# AND_operations.net
KiCad netlist of a schematic drawn in Altium Designer
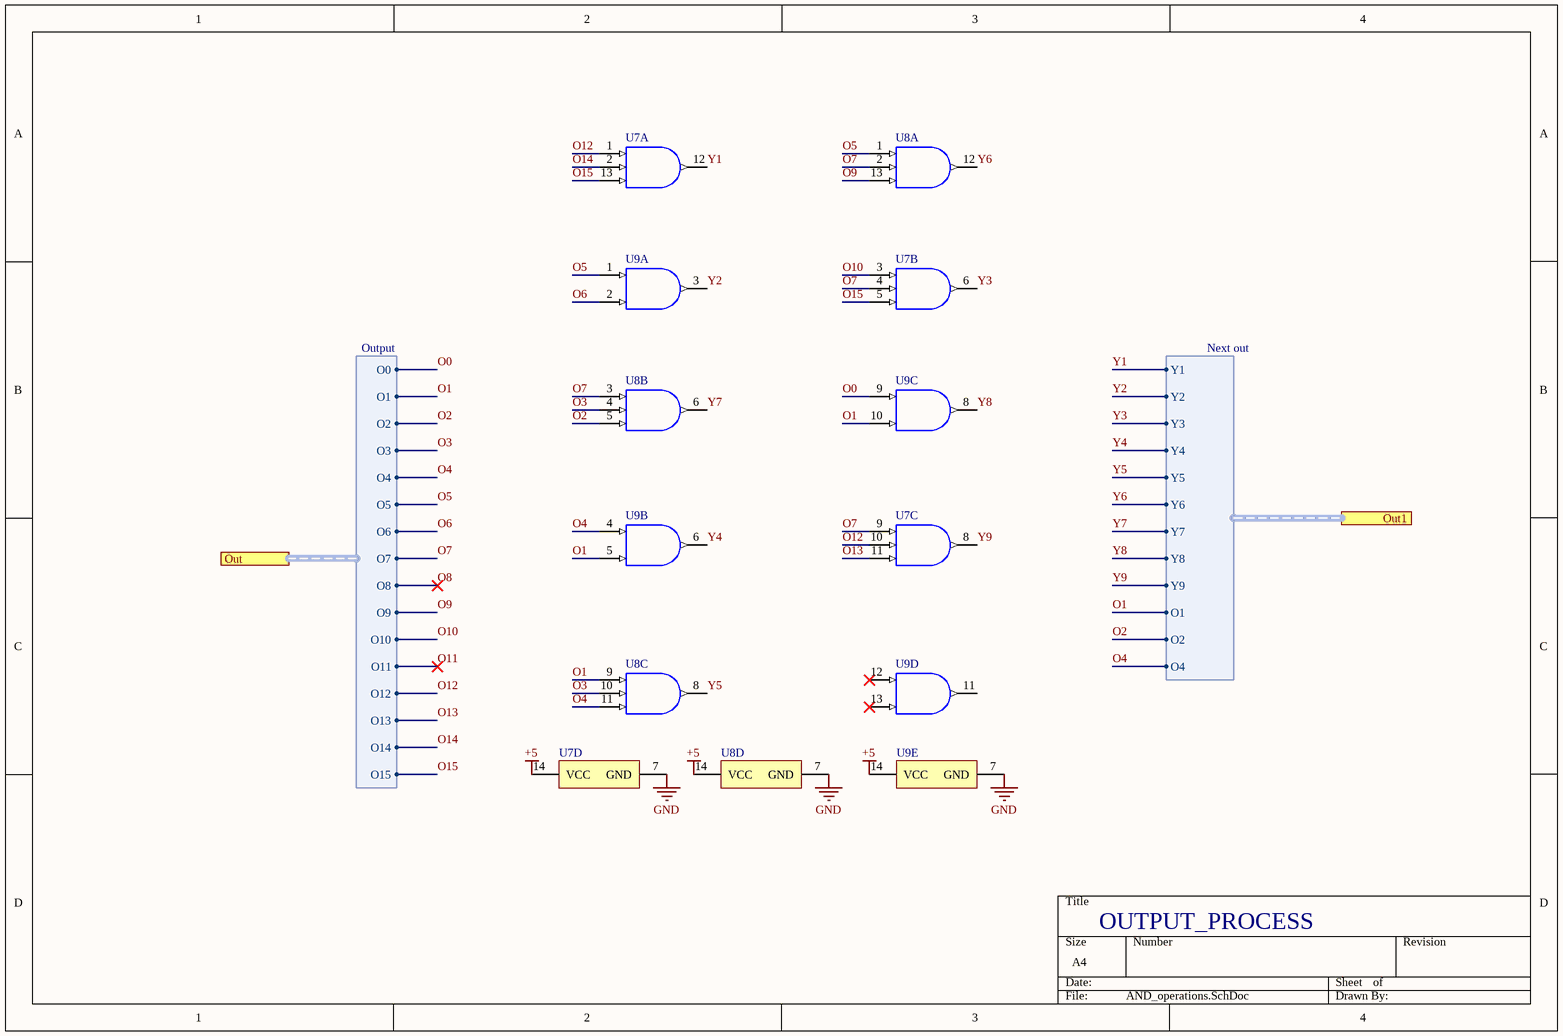
[diagram p0: AND_operations.SchDoc]

(export (version "E")
  (design (tool "Eeschema 10.0.6"))
  (components
    (comp (ref "U7")
      (value "SN74LS11N")
      (footprint "N0014A")
      (description "Triple 3-input positive-AND gates, N0014A, TUBE")
      (fields
        (field (name "MANUFACTURER") "Texas Instruments")
        (field (name "GENERIC PART NUMBER") "SN74LS11")
      )
      (libsource (lib "Altium Content Vault") (part "TI-AND-3-3IN-14"))
    )
    (comp (ref "U8")
      (value "SN74LS11N")
      (footprint "N0014A")
      (description "Triple 3-input positive-AND gates, N0014A, TUBE")
      (fields
        (field (name "MANUFACTURER") "Texas Instruments")
        (field (name "GENERIC PART NUMBER") "SN74LS11")
      )
      (libsource (lib "Altium Content Vault") (part "TI-AND-3-3IN-14"))
    )
    (comp (ref "U9")
      (value "SN74S08N")
      (footprint "N0014A")
      (description "Quad 2-input positive-AND gates, N0014A, TUBE")
      (fields
        (field (name "MANUFACTURER") "Texas Instruments")
        (field (name "GENERIC PART NUMBER") "SN74S08")
      )
      (libsource (lib "Altium Content Vault") (part "TI-AND-4-2IN-14"))
    )
  )
  (nets
    (net (code "4") (name "+5") (class "Default")
      (node (ref "U7") (pin "14") (pinfunction "VCC_14") (pintype "power_in"))
      (node (ref "U8") (pin "14") (pinfunction "VCC_14") (pintype "power_in"))
      (node (ref "U9") (pin "14") (pinfunction "VCC_14") (pintype "power_in"))
    )
    (net (code "5") (name "/O0") (class "Default")
      (node (ref "U9") (pin "9") (pinfunction "3A_9") (pintype "input"))
    )
    (net (code "6") (name "/O1") (class "Default")
      (node (ref "U8") (pin "9") (pinfunction "3A_9") (pintype "input"))
      (node (ref "U9") (pin "10") (pinfunction "3B_10") (pintype "input"))
      (node (ref "U9") (pin "5") (pinfunction "2B_5") (pintype "input"))
    )
    (net (code "7") (name "/O2") (class "Default")
      (node (ref "U8") (pin "5") (pinfunction "2C_5") (pintype "input"))
    )
    (net (code "8") (name "/O3") (class "Default")
      (node (ref "U8") (pin "10") (pinfunction "3B_10") (pintype "input"))
      (node (ref "U8") (pin "4") (pinfunction "2B_4") (pintype "input"))
    )
    (net (code "9") (name "/O4") (class "Default")
      (node (ref "U8") (pin "11") (pinfunction "3C_11") (pintype "input"))
      (node (ref "U9") (pin "4") (pinfunction "2A_4") (pintype "input"))
    )
    (net (code "10") (name "/O5") (class "Default")
      (node (ref "U8") (pin "1") (pinfunction "1A_1") (pintype "input"))
      (node (ref "U9") (pin "1") (pinfunction "1A_1") (pintype "input"))
    )
    (net (code "11") (name "/O6") (class "Default")
      (node (ref "U9") (pin "2") (pinfunction "1B_2") (pintype "input"))
    )
    (net (code "12") (name "/O7") (class "Default")
      (node (ref "U7") (pin "4") (pinfunction "2B_4") (pintype "input"))
      (node (ref "U7") (pin "9") (pinfunction "3A_9") (pintype "input"))
      (node (ref "U8") (pin "2") (pinfunction "1B_2") (pintype "input"))
      (node (ref "U8") (pin "3") (pinfunction "2A_3") (pintype "input"))
    )
    (net (code "14") (name "/O9") (class "Default")
      (node (ref "U8") (pin "13") (pinfunction "1C_13") (pintype "input"))
    )
    (net (code "15") (name "/O10") (class "Default")
      (node (ref "U7") (pin "3") (pinfunction "2A_3") (pintype "input"))
    )
    (net (code "17") (name "/O12") (class "Default")
      (node (ref "U7") (pin "1") (pinfunction "1A_1") (pintype "input"))
      (node (ref "U7") (pin "10") (pinfunction "3B_10") (pintype "input"))
    )
    (net (code "18") (name "/O13") (class "Default")
      (node (ref "U7") (pin "11") (pinfunction "3C_11") (pintype "input"))
    )
    (net (code "19") (name "/O14") (class "Default")
      (node (ref "U7") (pin "2") (pinfunction "1B_2") (pintype "input"))
    )
    (net (code "20") (name "/O15") (class "Default")
      (node (ref "U7") (pin "13") (pinfunction "1C_13") (pintype "input"))
      (node (ref "U7") (pin "5") (pinfunction "2C_5") (pintype "input"))
    )
    (net (code "21") (name "/Y1") (class "Default")
      (node (ref "U7") (pin "12") (pinfunction "1Y_12") (pintype "output"))
    )
    (net (code "22") (name "/Y2") (class "Default")
      (node (ref "U9") (pin "3") (pinfunction "1Y_3") (pintype "output"))
    )
    (net (code "23") (name "/Y3") (class "Default")
      (node (ref "U7") (pin "6") (pinfunction "2Y_6") (pintype "output"))
    )
    (net (code "24") (name "/Y4") (class "Default")
      (node (ref "U9") (pin "6") (pinfunction "2Y_6") (pintype "output"))
    )
    (net (code "25") (name "/Y5") (class "Default")
      (node (ref "U8") (pin "8") (pinfunction "3Y_8") (pintype "output"))
    )
    (net (code "26") (name "/Y6") (class "Default")
      (node (ref "U8") (pin "12") (pinfunction "1Y_12") (pintype "output"))
    )
    (net (code "27") (name "/Y7") (class "Default")
      (node (ref "U8") (pin "6") (pinfunction "2Y_6") (pintype "output"))
    )
    (net (code "28") (name "/Y8") (class "Default")
      (node (ref "U9") (pin "8") (pinfunction "3Y_8") (pintype "output"))
    )
    (net (code "29") (name "/Y9") (class "Default")
      (node (ref "U7") (pin "8") (pinfunction "3Y_8") (pintype "output"))
    )
    (net (code "32") (name "GND") (class "Default")
      (node (ref "U7") (pin "7") (pinfunction "GND_7") (pintype "power_in"))
      (node (ref "U8") (pin "7") (pinfunction "GND_7") (pintype "power_in"))
      (node (ref "U9") (pin "7") (pinfunction "GND_7") (pintype "power_in"))
    )
    (net (code "33") (name "unconnected-(U9D-4A-Pad12)") (class "Default")
      (node (ref "U9") (pin "12") (pinfunction "4A_12") (pintype "input+no_connect"))
    )
    (net (code "34") (name "unconnected-(U9D-4B-Pad13)") (class "Default")
      (node (ref "U9") (pin "13") (pinfunction "4B_13") (pintype "input+no_connect"))
    )
    (net (code "35") (name "unconnected-(U9D-4Y-Pad11)") (class "Default")
      (node (ref "U9") (pin "11") (pinfunction "4Y_11") (pintype "output"))
    )
  )
)
